# 3Sens_lowPass.net
KiCad netlist of a schematic drawn in EAGLE
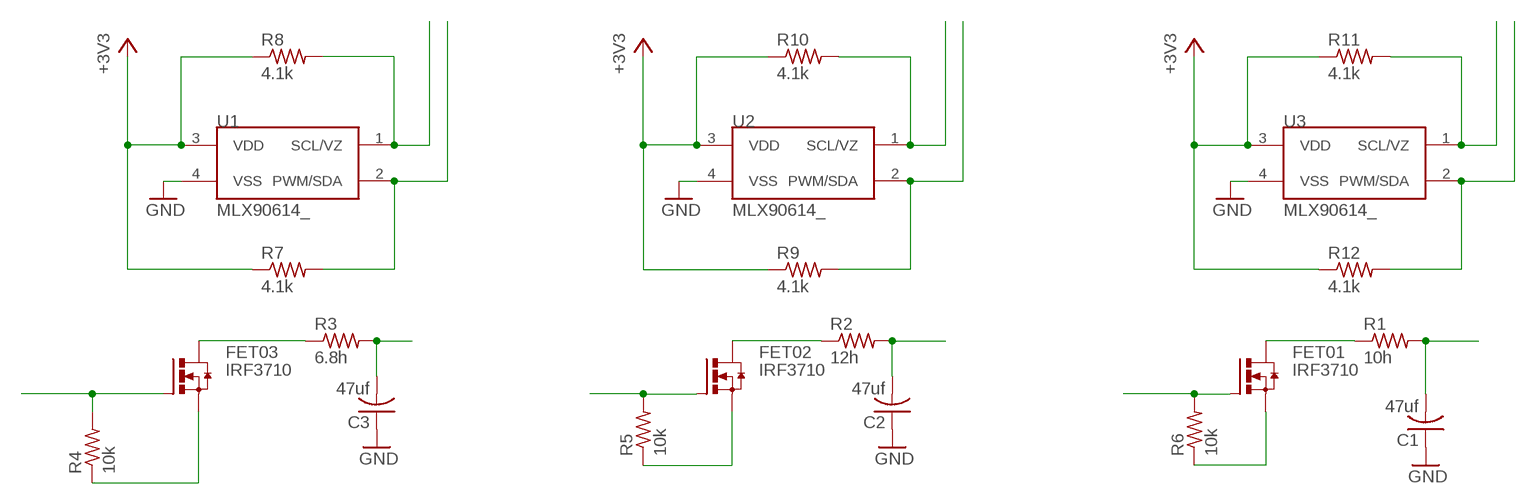
[diagram p0: schematic, sheet 1]

(export (version "E")
  (design (tool "Eeschema 10.0.6"))
  (components
    (comp (ref "C1")
      (value "47uf")
      (footprint "eagle-import:C025-024X044")
      (libsource (lib "eagle-import") (part "C-US025-024X044"))
    )
    (comp (ref "C2")
      (value "47uf")
      (footprint "eagle-import:C025-024X044")
      (libsource (lib "eagle-import") (part "C-US025-024X044"))
    )
    (comp (ref "C3")
      (value "47uf")
      (footprint "eagle-import:C025-024X044")
      (libsource (lib "eagle-import") (part "C-US025-024X044"))
    )
    (comp (ref "FET01")
      (value "IRF3710")
      (footprint "eagle-import:TO220AH")
      (libsource (lib "eagle-import") (part "IRF3704"))
    )
    (comp (ref "FET02")
      (value "IRF3710")
      (footprint "eagle-import:TO220AH")
      (libsource (lib "eagle-import") (part "IRF3704"))
    )
    (comp (ref "FET03")
      (value "IRF3710")
      (footprint "eagle-import:TO220AH")
      (libsource (lib "eagle-import") (part "IRF3704"))
    )
    (comp (ref "R1")
      (value "10h")
      (footprint "eagle-import:0204V")
      (libsource (lib "eagle-import") (part "R-US_0204/2V"))
    )
    (comp (ref "R2")
      (value "12h")
      (footprint "eagle-import:0204V")
      (libsource (lib "eagle-import") (part "R-US_0204/2V"))
    )
    (comp (ref "R3")
      (value "6.8h")
      (footprint "eagle-import:0204V")
      (libsource (lib "eagle-import") (part "R-US_0204/2V"))
    )
    (comp (ref "R4")
      (value "10k")
      (footprint "eagle-import:0204V")
      (libsource (lib "eagle-import") (part "R-US_0204/2V"))
    )
    (comp (ref "R5")
      (value "10k")
      (footprint "eagle-import:0204V")
      (libsource (lib "eagle-import") (part "R-US_0204/2V"))
    )
    (comp (ref "R6")
      (value "10k")
      (footprint "eagle-import:0204V")
      (libsource (lib "eagle-import") (part "R-US_0204/2V"))
    )
    (comp (ref "R7")
      (value "4.1k")
      (footprint "eagle-import:0204V")
      (libsource (lib "eagle-import") (part "R-US_0204/2V"))
    )
    (comp (ref "R8")
      (value "4.1k")
      (footprint "eagle-import:0204V")
      (libsource (lib "eagle-import") (part "R-US_0204/2V"))
    )
    (comp (ref "R9")
      (value "4.1k")
      (footprint "eagle-import:0204V")
      (libsource (lib "eagle-import") (part "R-US_0204/2V"))
    )
    (comp (ref "R10")
      (value "4.1k")
      (footprint "eagle-import:0204V")
      (libsource (lib "eagle-import") (part "R-US_0204/2V"))
    )
    (comp (ref "R11")
      (value "4.1k")
      (footprint "eagle-import:0204V")
      (libsource (lib "eagle-import") (part "R-US_0204/2V"))
    )
    (comp (ref "R12")
      (value "4.1k")
      (footprint "eagle-import:0204V")
      (libsource (lib "eagle-import") (part "R-US_0204/2V"))
    )
    (comp (ref "U1")
      (value "MLX90614_")
      (footprint "eagle-import:TO-39")
      (libsource (lib "eagle-import") (part "MLX90614_"))
    )
    (comp (ref "U2")
      (value "MLX90614_")
      (footprint "eagle-import:TO-39")
      (libsource (lib "eagle-import") (part "MLX90614_"))
    )
    (comp (ref "U3")
      (value "MLX90614_")
      (footprint "eagle-import:TO-39")
      (libsource (lib "eagle-import") (part "MLX90614_"))
    )
  )
  (nets
    (net (code "1") (name "+3V3") (class "Default")
      (node (ref "R10") (pin "1") (pinfunction "1_1") (pintype "passive"))
      (node (ref "R11") (pin "1") (pinfunction "1_1") (pintype "passive"))
      (node (ref "R12") (pin "1") (pinfunction "1_1") (pintype "passive"))
      (node (ref "R7") (pin "1") (pinfunction "1_1") (pintype "passive"))
      (node (ref "R8") (pin "1") (pinfunction "1_1") (pintype "passive"))
      (node (ref "R9") (pin "1") (pinfunction "1_1") (pintype "passive"))
      (node (ref "U1") (pin "3") (pinfunction "VDD_3") (pintype "bidirectional"))
      (node (ref "U2") (pin "3") (pinfunction "VDD_3") (pintype "bidirectional"))
      (node (ref "U3") (pin "3") (pinfunction "VDD_3") (pintype "bidirectional"))
    )
    (net (code "2") (name "GND") (class "Default")
      (node (ref "C1") (pin "1") (pinfunction "1_1") (pintype "passive"))
      (node (ref "C2") (pin "1") (pinfunction "1_1") (pintype "passive"))
      (node (ref "C3") (pin "1") (pinfunction "1_1") (pintype "passive"))
      (node (ref "U1") (pin "4") (pinfunction "VSS_4") (pintype "bidirectional"))
      (node (ref "U2") (pin "4") (pinfunction "VSS_4") (pintype "bidirectional"))
      (node (ref "U3") (pin "4") (pinfunction "VSS_4") (pintype "bidirectional"))
    )
    (net (code "3") (name "Net-(C1-Pad2)") (class "Default")
      (node (ref "C1") (pin "2") (pinfunction "2_2") (pintype "passive"))
      (node (ref "R1") (pin "2") (pinfunction "2_2") (pintype "passive"))
    )
    (net (code "4") (name "Net-(C2-Pad2)") (class "Default")
      (node (ref "C2") (pin "2") (pinfunction "2_2") (pintype "passive"))
      (node (ref "R2") (pin "2") (pinfunction "2_2") (pintype "passive"))
    )
    (net (code "5") (name "Net-(C3-Pad2)") (class "Default")
      (node (ref "C3") (pin "2") (pinfunction "2_2") (pintype "passive"))
      (node (ref "R3") (pin "2") (pinfunction "2_2") (pintype "passive"))
    )
    (net (code "6") (name "Net-(FET01-D)") (class "Default")
      (node (ref "FET01") (pin "C") (pinfunction "D_C") (pintype "passive"))
      (node (ref "R1") (pin "1") (pinfunction "1_1") (pintype "passive"))
    )
    (net (code "7") (name "Net-(FET01-G)") (class "Default")
      (node (ref "FET01") (pin "B") (pinfunction "G_B") (pintype "passive"))
      (node (ref "R6") (pin "2") (pinfunction "2_2") (pintype "passive"))
    )
    (net (code "8") (name "Net-(FET01-S)") (class "Default")
      (node (ref "FET01") (pin "E") (pinfunction "S_E") (pintype "passive"))
      (node (ref "R6") (pin "1") (pinfunction "1_1") (pintype "passive"))
    )
    (net (code "9") (name "Net-(FET02-D)") (class "Default")
      (node (ref "FET02") (pin "C") (pinfunction "D_C") (pintype "passive"))
      (node (ref "R2") (pin "1") (pinfunction "1_1") (pintype "passive"))
    )
    (net (code "10") (name "Net-(FET02-G)") (class "Default")
      (node (ref "FET02") (pin "B") (pinfunction "G_B") (pintype "passive"))
      (node (ref "R5") (pin "2") (pinfunction "2_2") (pintype "passive"))
    )
    (net (code "11") (name "Net-(FET02-S)") (class "Default")
      (node (ref "FET02") (pin "E") (pinfunction "S_E") (pintype "passive"))
      (node (ref "R5") (pin "1") (pinfunction "1_1") (pintype "passive"))
    )
    (net (code "12") (name "Net-(FET03-D)") (class "Default")
      (node (ref "FET03") (pin "C") (pinfunction "D_C") (pintype "passive"))
      (node (ref "R3") (pin "1") (pinfunction "1_1") (pintype "passive"))
    )
    (net (code "13") (name "Net-(FET03-G)") (class "Default")
      (node (ref "FET03") (pin "B") (pinfunction "G_B") (pintype "passive"))
      (node (ref "R4") (pin "2") (pinfunction "2_2") (pintype "passive"))
    )
    (net (code "14") (name "Net-(FET03-S)") (class "Default")
      (node (ref "FET03") (pin "E") (pinfunction "S_E") (pintype "passive"))
      (node (ref "R4") (pin "1") (pinfunction "1_1") (pintype "passive"))
    )
    (net (code "15") (name "Net-(U1-PWM{slash}SDA)") (class "Default")
      (node (ref "R7") (pin "2") (pinfunction "2_2") (pintype "passive"))
      (node (ref "U1") (pin "2") (pinfunction "PWM/SDA_2") (pintype "bidirectional"))
    )
    (net (code "16") (name "Net-(U1-SCL{slash}VZ)") (class "Default")
      (node (ref "R8") (pin "2") (pinfunction "2_2") (pintype "passive"))
      (node (ref "U1") (pin "1") (pinfunction "SCL/VZ_1") (pintype "bidirectional"))
    )
    (net (code "17") (name "Net-(U2-PWM{slash}SDA)") (class "Default")
      (node (ref "R9") (pin "2") (pinfunction "2_2") (pintype "passive"))
      (node (ref "U2") (pin "2") (pinfunction "PWM/SDA_2") (pintype "bidirectional"))
    )
    (net (code "18") (name "Net-(U2-SCL{slash}VZ)") (class "Default")
      (node (ref "R10") (pin "2") (pinfunction "2_2") (pintype "passive"))
      (node (ref "U2") (pin "1") (pinfunction "SCL/VZ_1") (pintype "bidirectional"))
    )
    (net (code "19") (name "Net-(U3-PWM{slash}SDA)") (class "Default")
      (node (ref "R12") (pin "2") (pinfunction "2_2") (pintype "passive"))
      (node (ref "U3") (pin "2") (pinfunction "PWM/SDA_2") (pintype "bidirectional"))
    )
    (net (code "20") (name "Net-(U3-SCL{slash}VZ)") (class "Default")
      (node (ref "R11") (pin "2") (pinfunction "2_2") (pintype "passive"))
      (node (ref "U3") (pin "1") (pinfunction "SCL/VZ_1") (pintype "bidirectional"))
    )
  )
)
